# TB906_HW_V1.net
KiCad netlist of a schematic drawn in Altium Designer
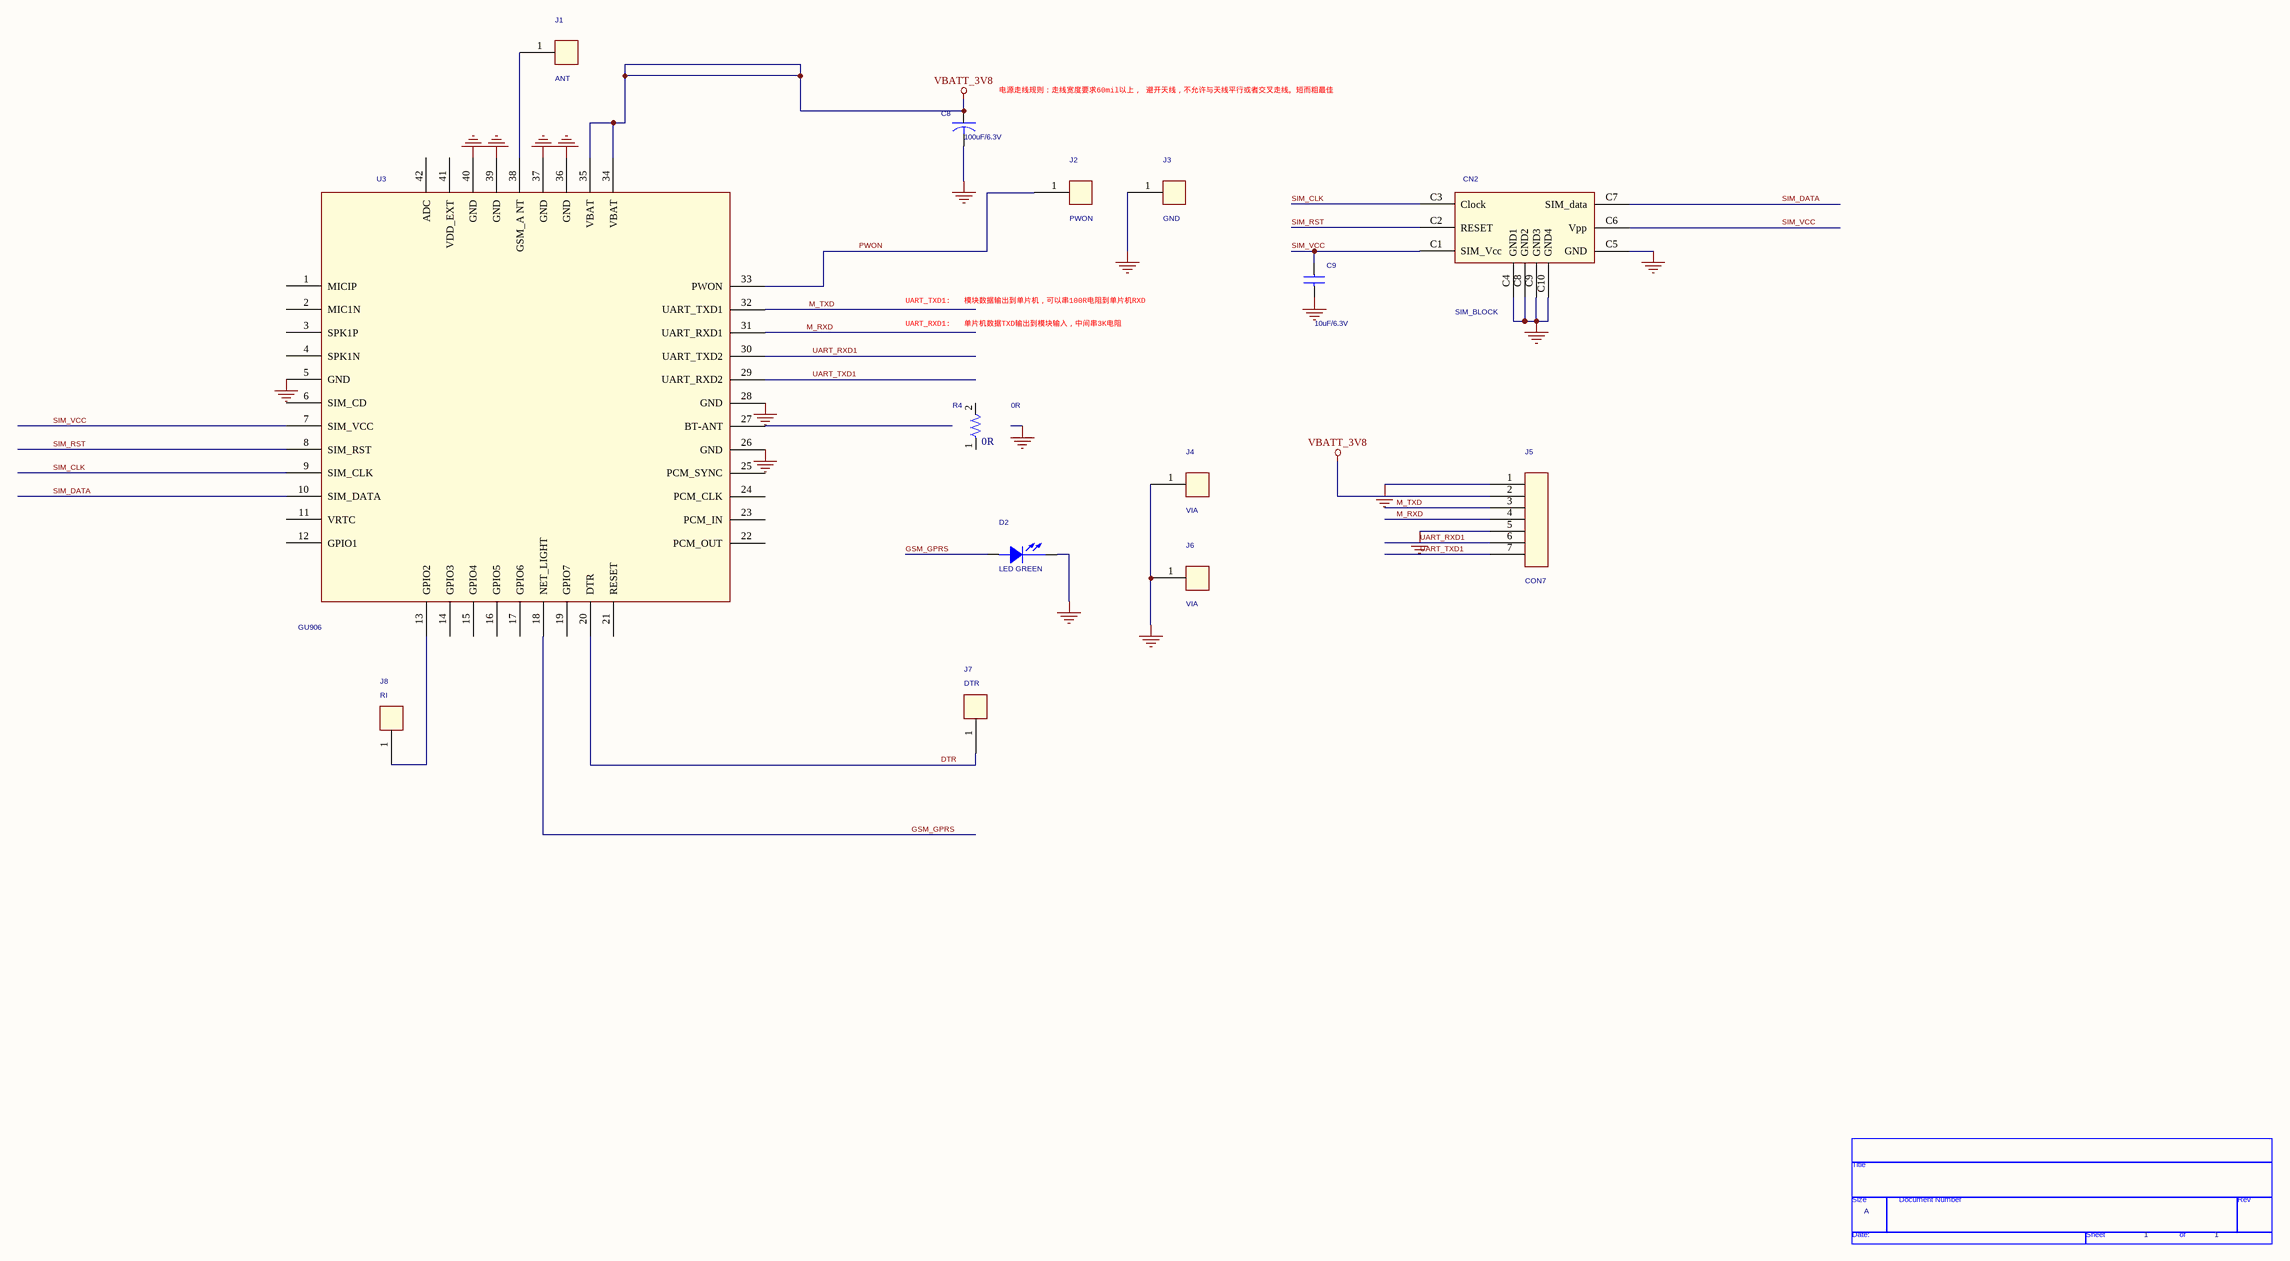
[diagram p0: TB906_HW V1.SchDoc]

(export (version "E")
  (design (tool "Eeschema 10.0.6"))
  (components
    (comp (ref "*")
      (value "TitleBlock0")
      (fields (field (name "PAGE COUNT") "1") (field (name "PAGE NUMBER") "1") (field (name "PAGE SIZE") "A"))
      (libsource (lib "*") (part "TitleBlock0"))
    )
    (comp (ref "C8") (value "100uF/6.3V") (libsource (lib "*") (part "CAP_5")))
    (comp (ref "C9") (value "10uF/6.3V") (libsource (lib "*") (part "CAP NP")))
    (comp (ref "CN2") (value "SIM_BLOCK") (footprint "SIM_BLOCK") (libsource (lib "*") (part "SIM_BLOCK_2")))
    (comp (ref "D2") (value "LED GREEN") (libsource (lib "*") (part "LED")))
    (comp (ref "J1") (value "ANT") (libsource (lib "*") (part "CON1")))
    (comp (ref "J2") (value "PWON") (libsource (lib "*") (part "CON1")))
    (comp (ref "J3") (value "GND") (libsource (lib "*") (part "CON1")))
    (comp (ref "J4") (value "VIA") (libsource (lib "*") (part "CON1")))
    (comp (ref "J5") (value "CON7") (libsource (lib "*") (part "CON7")))
    (comp (ref "J6") (value "VIA") (libsource (lib "*") (part "CON1")))
    (comp (ref "J7") (value "DTR") (libsource (lib "") (part "CON1_1")))
    (comp (ref "J8") (value "RI") (libsource (lib "") (part "CON1_1")))
    (comp (ref "R4")
      (value "0R")
      (footprint "AX/RC05")
      (fields (field (name "ALTIUM_VALUE") "0R"))
      (libsource (lib "*") (part "r"))
    )
    (comp (ref "U3") (value "GU906") (libsource (lib "*") (part "GU600_LIB_2")))
  )
  (nets
    (net (code "1") (name "/DTR") (class "Default")
      (node (ref "J7") (pin "1") (pinfunction "1_1") (pintype "passive"))
      (node (ref "U3") (pin "20") (pinfunction "DTR_20") (pintype "passive"))
    )
    (net (code "2") (name "/GSM_GPRS") (class "Default")
      (node (ref "D2") (pin "1") (pinfunction "ANODE_1") (pintype "passive"))
      (node (ref "U3") (pin "18") (pinfunction "NET_LIGHT_18") (pintype "passive"))
    )
    (net (code "3") (name "/M_RXD") (class "Default")
      (node (ref "J5") (pin "4") (pinfunction "4_4") (pintype "passive"))
      (node (ref "U3") (pin "31") (pinfunction "UART_RXD1_31") (pintype "passive"))
    )
    (net (code "4") (name "/M_TXD") (class "Default")
      (node (ref "J5") (pin "3") (pinfunction "3_3") (pintype "passive"))
      (node (ref "U3") (pin "32") (pinfunction "UART_TXD1_32") (pintype "passive"))
    )
    (net (code "5") (name "/PWON") (class "Default")
      (node (ref "J2") (pin "1") (pinfunction "1_1") (pintype "passive"))
      (node (ref "U3") (pin "33") (pinfunction "PWON_33") (pintype "passive"))
    )
    (net (code "6") (name "/SIM_CLK") (class "Default")
      (node (ref "CN2") (pin "C3") (pinfunction "Clock_C3") (pintype "passive"))
      (node (ref "U3") (pin "9") (pinfunction "SIM_CLK_9") (pintype "passive"))
    )
    (net (code "7") (name "/SIM_DATA") (class "Default")
      (node (ref "CN2") (pin "C7") (pinfunction "SIM_data_C7") (pintype "passive"))
      (node (ref "U3") (pin "10") (pinfunction "SIM_DATA_10") (pintype "passive"))
    )
    (net (code "8") (name "/SIM_RST") (class "Default")
      (node (ref "CN2") (pin "C2") (pinfunction "RESET_C2") (pintype "passive"))
      (node (ref "U3") (pin "8") (pinfunction "SIM_RST_8") (pintype "passive"))
    )
    (net (code "9") (name "/SIM_VCC") (class "Default")
      (node (ref "C9") (pin "1") (pinfunction "1_1") (pintype "passive"))
      (node (ref "CN2") (pin "C1") (pinfunction "SIM_Vcc_C1") (pintype "passive"))
      (node (ref "CN2") (pin "C6") (pinfunction "Vpp_C6") (pintype "passive"))
      (node (ref "U3") (pin "7") (pinfunction "SIM_VCC_7") (pintype "passive"))
    )
    (net (code "10") (name "/UART_RXD1") (class "Default")
      (node (ref "J5") (pin "6") (pinfunction "6_6") (pintype "passive"))
      (node (ref "U3") (pin "30") (pinfunction "UART_TXD2_30") (pintype "passive"))
    )
    (net (code "11") (name "/UART_TXD1") (class "Default")
      (node (ref "J5") (pin "7") (pinfunction "7_7") (pintype "passive"))
      (node (ref "U3") (pin "29") (pinfunction "UART_RXD2_29") (pintype "passive"))
    )
    (net (code "12") (name "GND") (class "Default")
      (node (ref "C8") (pin "2") (pinfunction "2_2") (pintype "passive"))
      (node (ref "C9") (pin "2") (pinfunction "2_2") (pintype "passive"))
      (node (ref "CN2") (pin "C10") (pinfunction "GND4_C10") (pintype "passive"))
      (node (ref "CN2") (pin "C4") (pinfunction "GND1_C4") (pintype "passive"))
      (node (ref "CN2") (pin "C5") (pinfunction "GND_C5") (pintype "passive"))
      (node (ref "CN2") (pin "C8") (pinfunction "GND2_C8") (pintype "passive"))
      (node (ref "CN2") (pin "C9") (pinfunction "GND3_C9") (pintype "passive"))
      (node (ref "D2") (pin "2") (pinfunction "CATHODE_2") (pintype "passive"))
      (node (ref "J3") (pin "1") (pinfunction "1_1") (pintype "passive"))
      (node (ref "J4") (pin "1") (pinfunction "1_1") (pintype "passive"))
      (node (ref "J5") (pin "1") (pinfunction "1_1") (pintype "passive"))
      (node (ref "J5") (pin "5") (pinfunction "5_5") (pintype "passive"))
      (node (ref "J6") (pin "1") (pinfunction "1_1") (pintype "passive"))
      (node (ref "U3") (pin "26") (pinfunction "GND_26") (pintype "passive"))
      (node (ref "U3") (pin "28") (pinfunction "GND_28") (pintype "passive"))
      (node (ref "U3") (pin "36") (pinfunction "GND_36") (pintype "passive"))
      (node (ref "U3") (pin "37") (pinfunction "GND_37") (pintype "passive"))
      (node (ref "U3") (pin "39") (pinfunction "GND_39") (pintype "passive"))
      (node (ref "U3") (pin "40") (pinfunction "GND_40") (pintype "passive"))
      (node (ref "U3") (pin "5") (pinfunction "GND_5") (pintype "passive"))
    )
    (net (code "13") (name "Net-(U3-GPIO2)") (class "Default")
      (node (ref "J8") (pin "1") (pinfunction "1_1") (pintype "passive"))
      (node (ref "U3") (pin "13") (pinfunction "GPIO2_13") (pintype "passive"))
    )
    (net (code "14") (name "Net-(U3-GSM_A_NT)") (class "Default")
      (node (ref "J1") (pin "1") (pinfunction "1_1") (pintype "passive"))
      (node (ref "U3") (pin "38") (pinfunction "GSM_A_NT_38") (pintype "passive"))
    )
    (net (code "15") (name "VBATT_3V8") (class "Default")
      (node (ref "C8") (pin "1") (pinfunction "1_1") (pintype "passive"))
      (node (ref "J5") (pin "2") (pinfunction "2_2") (pintype "passive"))
      (node (ref "U3") (pin "34") (pinfunction "VBAT_34") (pintype "passive"))
      (node (ref "U3") (pin "35") (pinfunction "VBAT_35") (pintype "passive"))
    )
    (net (code "16") (name "unconnected-(R4-Pad1)") (class "Default")
      (node (ref "R4") (pin "1") (pinfunction "1_1") (pintype "passive"))
    )
    (net (code "17") (name "unconnected-(R4-Pad2)") (class "Default")
      (node (ref "R4") (pin "2") (pinfunction "2_2") (pintype "passive"))
    )
    (net (code "18") (name "unconnected-(U3-ADC-Pad42)") (class "Default")
      (node (ref "U3") (pin "42") (pinfunction "ADC_42") (pintype "passive"))
    )
    (net (code "19") (name "unconnected-(U3-BT-ANT-Pad27)") (class "Default")
      (node (ref "U3") (pin "27") (pinfunction "BT-ANT_27") (pintype "passive"))
    )
    (net (code "20") (name "unconnected-(U3-GPIO1-Pad12)") (class "Default")
      (node (ref "U3") (pin "12") (pinfunction "GPIO1_12") (pintype "passive"))
    )
    (net (code "21") (name "unconnected-(U3-GPIO3-Pad14)") (class "Default")
      (node (ref "U3") (pin "14") (pinfunction "GPIO3_14") (pintype "passive"))
    )
    (net (code "22") (name "unconnected-(U3-GPIO4-Pad15)") (class "Default")
      (node (ref "U3") (pin "15") (pinfunction "GPIO4_15") (pintype "passive"))
    )
    (net (code "23") (name "unconnected-(U3-GPIO5-Pad16)") (class "Default")
      (node (ref "U3") (pin "16") (pinfunction "GPIO5_16") (pintype "passive"))
    )
    (net (code "24") (name "unconnected-(U3-GPIO6-Pad17)") (class "Default")
      (node (ref "U3") (pin "17") (pinfunction "GPIO6_17") (pintype "passive"))
    )
    (net (code "25") (name "unconnected-(U3-GPIO7-Pad19)") (class "Default")
      (node (ref "U3") (pin "19") (pinfunction "GPIO7_19") (pintype "passive"))
    )
    (net (code "26") (name "unconnected-(U3-MIC1N-Pad2)") (class "Default")
      (node (ref "U3") (pin "2") (pinfunction "MIC1N_2") (pintype "passive"))
    )
    (net (code "27") (name "unconnected-(U3-MICIP-Pad1)") (class "Default")
      (node (ref "U3") (pin "1") (pinfunction "MICIP_1") (pintype "passive"))
    )
    (net (code "28") (name "unconnected-(U3-PCM_CLK-Pad24)") (class "Default")
      (node (ref "U3") (pin "24") (pinfunction "PCM_CLK_24") (pintype "passive"))
    )
    (net (code "29") (name "unconnected-(U3-PCM_IN-Pad23)") (class "Default")
      (node (ref "U3") (pin "23") (pinfunction "PCM_IN_23") (pintype "passive"))
    )
    (net (code "30") (name "unconnected-(U3-PCM_OUT-Pad22)") (class "Default")
      (node (ref "U3") (pin "22") (pinfunction "PCM_OUT_22") (pintype "passive"))
    )
    (net (code "31") (name "unconnected-(U3-PCM_SYNC-Pad25)") (class "Default")
      (node (ref "U3") (pin "25") (pinfunction "PCM_SYNC_25") (pintype "passive"))
    )
    (net (code "32") (name "unconnected-(U3-RESET-Pad21)") (class "Default")
      (node (ref "U3") (pin "21") (pinfunction "RESET_21") (pintype "passive"))
    )
    (net (code "33") (name "unconnected-(U3-SIM_CD-Pad6)") (class "Default")
      (node (ref "U3") (pin "6") (pinfunction "SIM_CD_6") (pintype "passive"))
    )
    (net (code "34") (name "unconnected-(U3-SPK1N-Pad4)") (class "Default")
      (node (ref "U3") (pin "4") (pinfunction "SPK1N_4") (pintype "passive"))
    )
    (net (code "35") (name "unconnected-(U3-SPK1P-Pad3)") (class "Default")
      (node (ref "U3") (pin "3") (pinfunction "SPK1P_3") (pintype "passive"))
    )
    (net (code "36") (name "unconnected-(U3-VDD_EXT-Pad41)") (class "Default")
      (node (ref "U3") (pin "41") (pinfunction "VDD_EXT_41") (pintype "passive"))
    )
    (net (code "37") (name "unconnected-(U3-VRTC-Pad11)") (class "Default")
      (node (ref "U3") (pin "11") (pinfunction "VRTC_11") (pintype "passive"))
    )
  )
)
